# ESP_Robo_Board_2.net
KiCad netlist of a schematic drawn in EAGLE
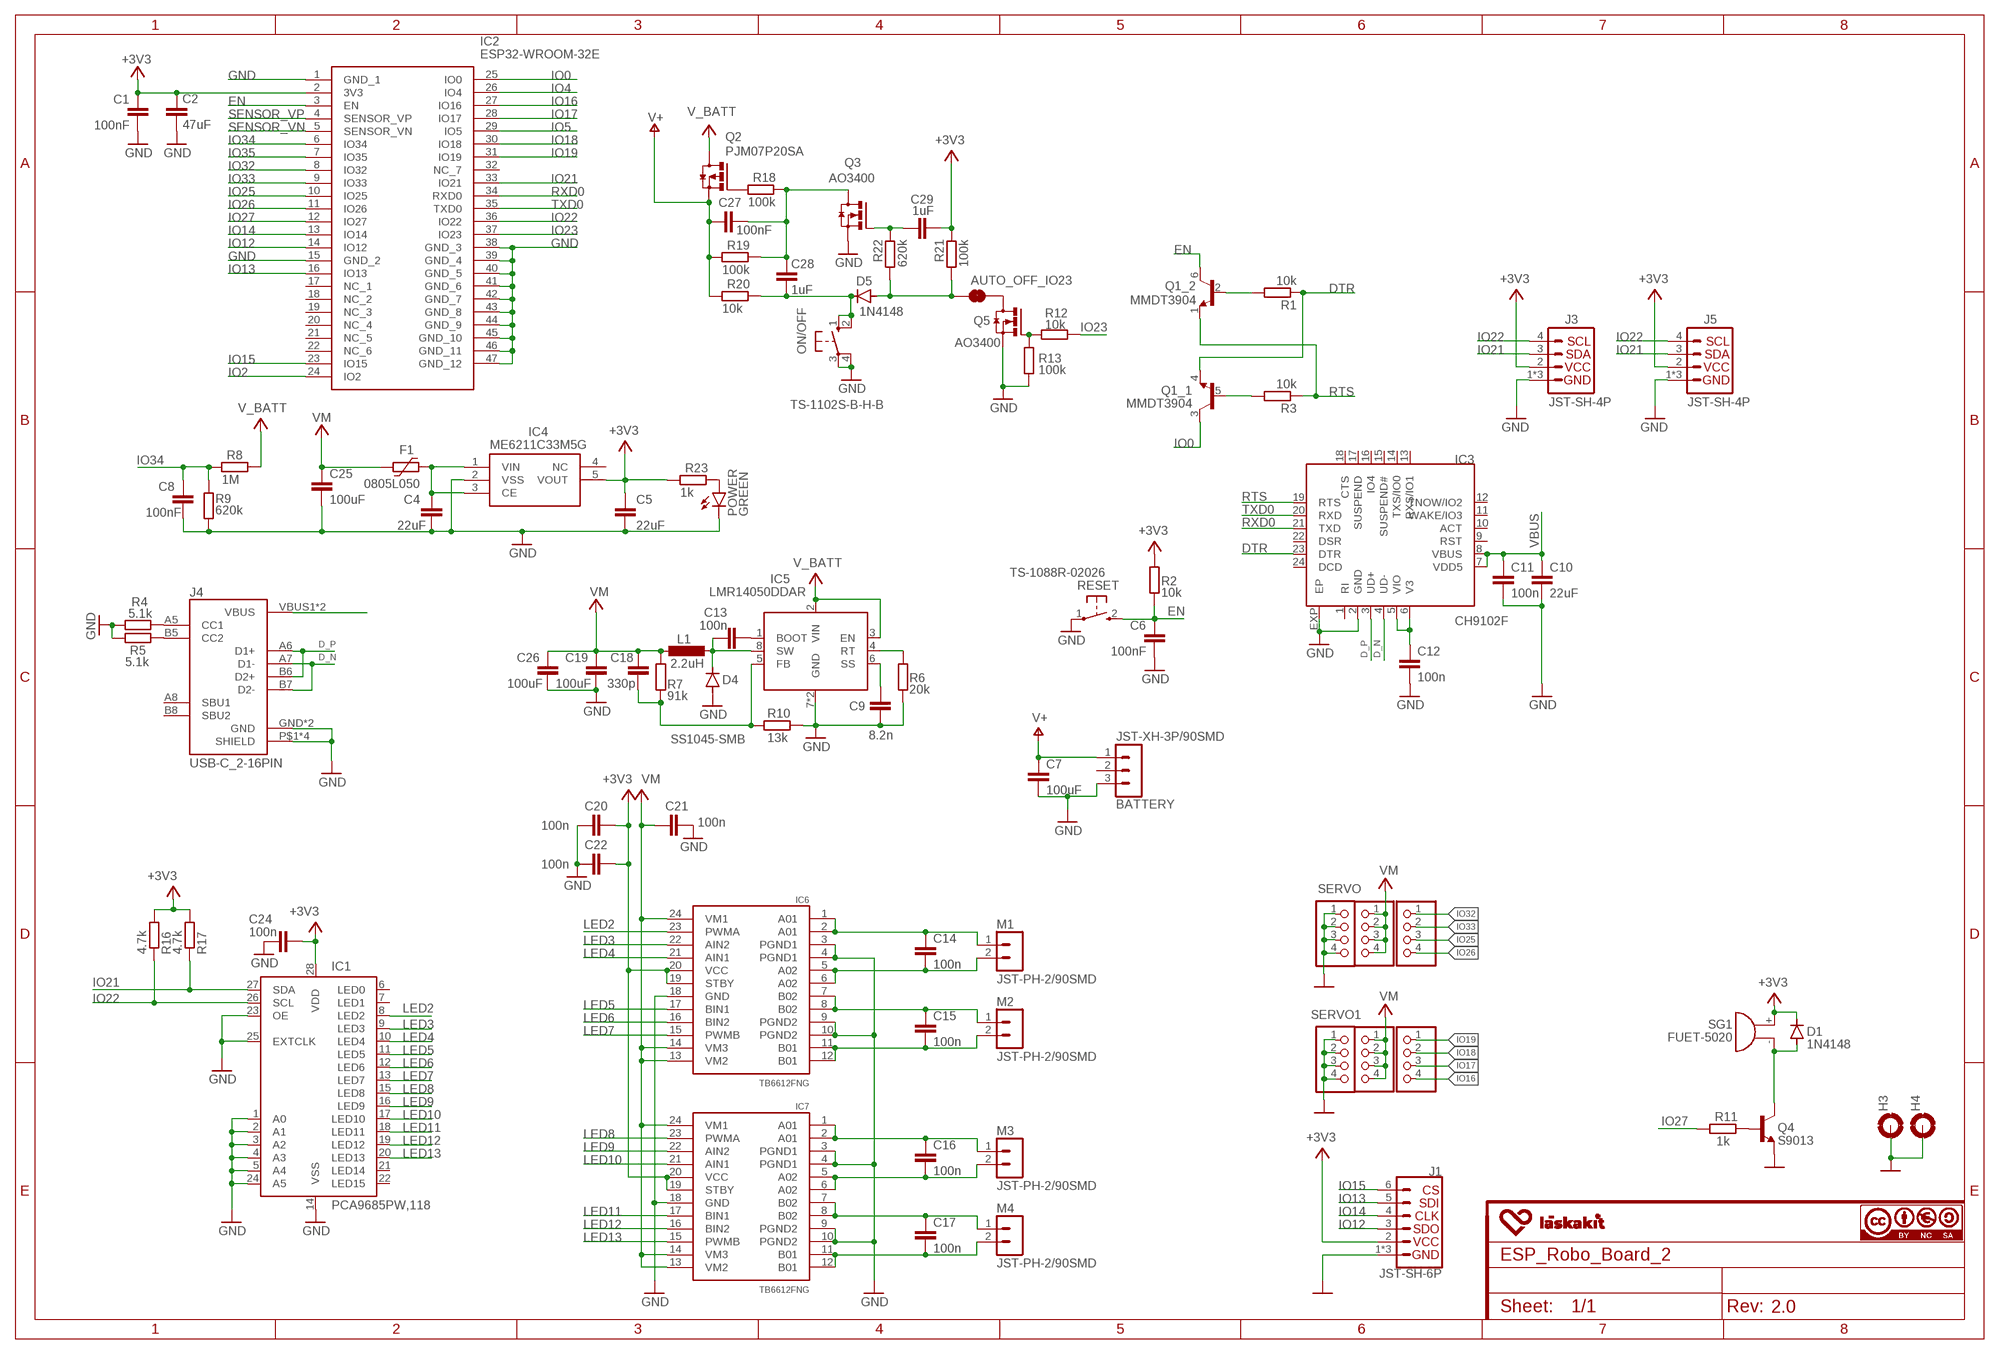
[diagram p0: schematic, sheet 1]

(export (version "E")
  (design (tool "Eeschema 10.0.6"))
  (components
    (comp (ref "1")
      (value "PINHD_1X4_RED")
      (footprint "eagle-import:1X04")
      (libsource (lib "eagle-import") (part "PINHD-1X4"))
    )
    (comp (ref "2")
      (value "PINHD_1X4_BLACK")
      (footprint "eagle-import:1X04")
      (libsource (lib "eagle-import") (part "PINHD-1X4"))
    )
    (comp (ref "5")
      (value "PINHD_1X4_RED")
      (footprint "eagle-import:1X04")
      (libsource (lib "eagle-import") (part "PINHD-1X4"))
    )
    (comp (ref "6")
      (value "PINHD_1X4_BLACK")
      (footprint "eagle-import:1X04")
      (libsource (lib "eagle-import") (part "PINHD-1X4"))
    )
    (comp (ref "AUTO_OFF_IO23")
      (value "nv")
      (footprint "eagle-import:SMT-JUMPER_2_NC_TRACE_SILK")
      (libsource (lib "eagle-import") (part "JUMPER-SMT_2_NC_TRACE_SILK"))
    )
    (comp (ref "BATTERY")
      (value "JST-XH-3P/90SMD")
      (footprint "eagle-import:S3B-XH-SM4")
      (libsource (lib "eagle-import") (part "JST-XH-3/90SMD"))
    )
    (comp (ref "C1")
      (value "100nF")
      (footprint "eagle-import:C0603")
      (libsource (lib "eagle-import") (part "C-EUC0603"))
    )
    (comp (ref "C2")
      (value "47uF")
      (footprint "eagle-import:C0805")
      (libsource (lib "eagle-import") (part "C-EUC0805"))
    )
    (comp (ref "C4")
      (value "22uF")
      (footprint "eagle-import:C0603")
      (libsource (lib "eagle-import") (part "C-EUC0603"))
    )
    (comp (ref "C5")
      (value "22uF")
      (footprint "eagle-import:C0603")
      (fields (field (name "LCSC_PART") "C19666"))
      (libsource (lib "eagle-import") (part "C-EUC0603"))
    )
    (comp (ref "C6")
      (value "100nF")
      (footprint "eagle-import:C0402")
      (libsource (lib "eagle-import") (part "CAPACITOR_0402"))
    )
    (comp (ref "C7")
      (value "100uF")
      (footprint "eagle-import:C1206")
      (libsource (lib "eagle-import") (part "C-EUC1206"))
    )
    (comp (ref "C8")
      (value "100nF")
      (footprint "eagle-import:C0402")
      (libsource (lib "eagle-import") (part "CAPACITOR_0402"))
    )
    (comp (ref "C9")
      (value "8.2n")
      (footprint "eagle-import:C0603")
      (libsource (lib "eagle-import") (part "C-EUC0603"))
    )
    (comp (ref "C10")
      (value "22uF")
      (footprint "eagle-import:C0603")
      (libsource (lib "eagle-import") (part "C-EUC0603"))
    )
    (comp (ref "C11")
      (value "100n")
      (footprint "eagle-import:C0402")
      (libsource (lib "eagle-import") (part "CAPACITOR_0402"))
    )
    (comp (ref "C12")
      (value "100n")
      (footprint "eagle-import:C0402")
      (libsource (lib "eagle-import") (part "CAPACITOR_0402"))
    )
    (comp (ref "C13")
      (value "100n")
      (footprint "eagle-import:C0603")
      (libsource (lib "eagle-import") (part "C-EUC0603"))
    )
    (comp (ref "C14")
      (value "100n")
      (footprint "eagle-import:C0603")
      (libsource (lib "eagle-import") (part "C-EUC0603"))
    )
    (comp (ref "C15")
      (value "100n")
      (footprint "eagle-import:C0603")
      (libsource (lib "eagle-import") (part "C-EUC0603"))
    )
    (comp (ref "C16")
      (value "100n")
      (footprint "eagle-import:C0603")
      (libsource (lib "eagle-import") (part "C-EUC0603"))
    )
    (comp (ref "C17")
      (value "100n")
      (footprint "eagle-import:C0603")
      (libsource (lib "eagle-import") (part "C-EUC0603"))
    )
    (comp (ref "C18")
      (value "330p")
      (footprint "eagle-import:C0402")
      (libsource (lib "eagle-import") (part "CAPACITOR_0402"))
    )
    (comp (ref "C19")
      (value "100uF")
      (footprint "eagle-import:C1206")
      (libsource (lib "eagle-import") (part "C-EUC1206"))
    )
    (comp (ref "C20")
      (value "100n")
      (footprint "eagle-import:C0603")
      (libsource (lib "eagle-import") (part "C-EUC0603"))
    )
    (comp (ref "C21")
      (value "100n")
      (footprint "eagle-import:C0603")
      (libsource (lib "eagle-import") (part "C-EUC0603"))
    )
    (comp (ref "C22")
      (value "100n")
      (footprint "eagle-import:C0603")
      (libsource (lib "eagle-import") (part "C-EUC0603"))
    )
    (comp (ref "C24")
      (value "100n")
      (footprint "eagle-import:C0603")
      (libsource (lib "eagle-import") (part "C-EUC0603"))
    )
    (comp (ref "C25")
      (value "100uF")
      (footprint "eagle-import:C1206")
      (libsource (lib "eagle-import") (part "C-EUC1206"))
    )
    (comp (ref "C26")
      (value "100uF")
      (footprint "eagle-import:C1206")
      (libsource (lib "eagle-import") (part "C-EUC1206"))
    )
    (comp (ref "C27")
      (value "100nF")
      (footprint "eagle-import:C0402")
      (libsource (lib "eagle-import") (part "CAPACITOR_0402"))
    )
    (comp (ref "C28")
      (value "1uF")
      (footprint "eagle-import:C0603")
      (libsource (lib "eagle-import") (part "C-EUC0603"))
    )
    (comp (ref "C29")
      (value "1uF")
      (footprint "eagle-import:C0603")
      (libsource (lib "eagle-import") (part "C-EUC0603"))
    )
    (comp (ref "D1")
      (value "1N4148")
      (footprint "eagle-import:SOD323-R")
      (fields (field (name "LCSC_PART") "C94001"))
      (libsource (lib "eagle-import") (part "DIODE-SOD323-R"))
    )
    (comp (ref "D4")
      (value "SS1045-SMB")
      (footprint "eagle-import:SMB")
      (fields (field (name "LCSC_PART") "C2903947"))
      (libsource (lib "eagle-import") (part "DIODE-SMB"))
    )
    (comp (ref "D5")
      (value "1N4148")
      (footprint "eagle-import:SOD323-R")
      (libsource (lib "eagle-import") (part "DIODE-SOD323-R"))
    )
    (comp (ref "F1")
      (value "0805L050")
      (footprint "eagle-import:0805L")
      (fields (field (name "MF") "Littelfuse") (field (name "LCSC_PART") "C66452"))
      (libsource (lib "eagle-import") (part "?0805L050"))
    )
    (comp (ref "H3")
      (value "MOUNT-PAD-ROUND2.5")
      (footprint "eagle-import:2,5-PAD")
      (libsource (lib "eagle-import") (part "MOUNT-PAD-ROUND2.5"))
    )
    (comp (ref "H4")
      (value "MOUNT-PAD-ROUND2.5")
      (footprint "eagle-import:2,5-PAD")
      (libsource (lib "eagle-import") (part "MOUNT-PAD-ROUND2.5"))
    )
    (comp (ref "IC1")
      (value "PCA9685PW,118")
      (footprint "eagle-import:TSSOP28")
      (fields (field (name "LCSC_PART") "C2678753"))
      (libsource (lib "eagle-import") (part "PCA9685PW,118"))
    )
    (comp (ref "IC2")
      (value "ESP32-WROOM-32E")
      (footprint "eagle-import:ESP32WROOM32E")
      (libsource (lib "eagle-import") (part "ESP32-WROOM-32E"))
    )
    (comp (ref "IC3")
      (value "CH9102F")
      (footprint "eagle-import:QFN24-4X4")
      (libsource (lib "eagle-import") (part "USB_UART_CONVERTOR_CH9102"))
    )
    (comp (ref "IC4")
      (value "ME6211C33M5G")
      (footprint "eagle-import:SOT23-5")
      (libsource (lib "eagle-import") (part "LDO_ME6211C33M5G"))
    )
    (comp (ref "IC5")
      (value "LMR14050DDAR")
      (footprint "eagle-import:SO08-EPAD")
      (fields (field (name "LCSC_PART") "C155484"))
      (libsource (lib "eagle-import") (part "LMR14050DDAR"))
    )
    (comp (ref "IC6")
      (value "TB6612FNG")
      (footprint "eagle-import:SSOP24")
      (libsource (lib "eagle-import") (part "MOTOR_DRIVER_TB6612FNG"))
    )
    (comp (ref "IC7")
      (value "TB6612FNG")
      (footprint "eagle-import:SSOP24")
      (libsource (lib "eagle-import") (part "MOTOR_DRIVER_TB6612FNG"))
    )
    (comp (ref "J1")
      (value "JST-SH-6P")
      (footprint "eagle-import:1X06_1MM_RA_VERT")
      (fields (field (name "LCSC_PART") "C145963"))
      (libsource (lib "eagle-import") (part "USUP_SPI_CONNECTOR_VERT"))
    )
    (comp (ref "J3")
      (value "JST-SH-4P")
      (footprint "eagle-import:1X04_1MM_RA_VERT")
      (fields (field (name "LCSC_PART") "C371588"))
      (libsource (lib "eagle-import") (part "USUP_I2C_CONNECTOR_VERT"))
    )
    (comp (ref "J4")
      (value "USB-C_2-16PIN")
      (footprint "eagle-import:USBC_USB-C-16P-5")
      (fields (field (name "LCSC_PART") "C2837092"))
      (libsource (lib "eagle-import") (part "USB-C_2-16PIN"))
    )
    (comp (ref "J5")
      (value "JST-SH-4P")
      (footprint "eagle-import:1X04_1MM_RA_VERT")
      (fields (field (name "LCSC_PART") "C371588"))
      (libsource (lib "eagle-import") (part "USUP_I2C_CONNECTOR_VERT"))
    )
    (comp (ref "L1")
      (value "2.2uH")
      (footprint "eagle-import:L5.4X5.2")
      (fields (field (name "LCSC_PART") "C351096"))
      (libsource (lib "eagle-import") (part "INDUCTOR_5.4X5.2"))
    )
    (comp (ref "M1")
      (value "JST-PH-2/90SMD")
      (footprint "eagle-import:S2B-PH-SM4")
      (fields (field (name "LCSC_PART") "C47647"))
      (libsource (lib "eagle-import") (part "JST-PH-2/90SMD"))
    )
    (comp (ref "M2")
      (value "JST-PH-2/90SMD")
      (footprint "eagle-import:S2B-PH-SM4")
      (fields (field (name "LCSC_PART") "C47647"))
      (libsource (lib "eagle-import") (part "JST-PH-2/90SMD"))
    )
    (comp (ref "M3")
      (value "JST-PH-2/90SMD")
      (footprint "eagle-import:S2B-PH-SM4")
      (fields (field (name "LCSC_PART") "C47647"))
      (libsource (lib "eagle-import") (part "JST-PH-2/90SMD"))
    )
    (comp (ref "M4")
      (value "JST-PH-2/90SMD")
      (footprint "eagle-import:S2B-PH-SM4")
      (fields (field (name "LCSC_PART") "C47647"))
      (libsource (lib "eagle-import") (part "JST-PH-2/90SMD"))
    )
    (comp (ref "ON/OFF")
      (value "TS-1102S-B-H-B")
      (footprint "eagle-import:B3F-SMD")
      (libsource (lib "eagle-import") (part "10-XX-SMD"))
    )
    (comp (ref "POWER")
      (value "GREEN")
      (footprint "eagle-import:CHIPLED_0402")
      (libsource (lib "eagle-import") (part "LEDCHIPLED_0402"))
    )
    (comp (ref "Q1")
      (value "MMDT3904")
      (footprint "eagle-import:SC70-6")
      (fields (field (name "LCSC_PART") "C268586"))
      (libsource (lib "eagle-import") (part "TRANS_NPN_DUAL-MBT3904DW1T1"))
    )
    (comp (ref "Q2")
      (value "PJM07P20SA")
      (footprint "eagle-import:SOT23")
      (fields (field (name "LCSC_PART") "C2856842"))
      (libsource (lib "eagle-import") (part "MOSFET_P-SOT-23"))
    )
    (comp (ref "Q3")
      (value "AO3400")
      (footprint "eagle-import:SOT23")
      (fields (field (name "LCSC_PART") "C693097"))
      (libsource (lib "eagle-import") (part "MOSFET_N-SOT-23"))
    )
    (comp (ref "Q4")
      (value "S9013")
      (footprint "eagle-import:SOT23-BEC")
      (fields (field (name "LCSC_PART") "C52801"))
      (libsource (lib "eagle-import") (part "-NPN-SOT23-BECBC817-16"))
    )
    (comp (ref "Q5")
      (value "AO3400")
      (footprint "eagle-import:SOT23")
      (fields (field (name "LCSC_PART") "C693097"))
      (libsource (lib "eagle-import") (part "MOSFET_N-SOT-23"))
    )
    (comp (ref "R1")
      (value "10k")
      (footprint "eagle-import:R0402")
      (libsource (lib "eagle-import") (part "R-EU_R0402"))
    )
    (comp (ref "R2")
      (value "10k")
      (footprint "eagle-import:R0402")
      (libsource (lib "eagle-import") (part "R-EU_R0402"))
    )
    (comp (ref "R3")
      (value "10k")
      (footprint "eagle-import:R0402")
      (libsource (lib "eagle-import") (part "R-EU_R0402"))
    )
    (comp (ref "R4")
      (value "5.1k")
      (footprint "eagle-import:R0402")
      (libsource (lib "eagle-import") (part "R-EU_R0402"))
    )
    (comp (ref "R5")
      (value "5.1k")
      (footprint "eagle-import:R0402")
      (libsource (lib "eagle-import") (part "R-EU_R0402"))
    )
    (comp (ref "R6")
      (value "20k")
      (footprint "eagle-import:R0402")
      (libsource (lib "eagle-import") (part "R-EU_R0402"))
    )
    (comp (ref "R7")
      (value "91k")
      (footprint "eagle-import:R0402")
      (libsource (lib "eagle-import") (part "R-EU_R0402"))
    )
    (comp (ref "R8")
      (value "1M")
      (footprint "eagle-import:R0402")
      (libsource (lib "eagle-import") (part "R-EU_R0402"))
    )
    (comp (ref "R9")
      (value "620k")
      (footprint "eagle-import:R0402")
      (libsource (lib "eagle-import") (part "R-EU_R0402"))
    )
    (comp (ref "R10")
      (value "13k")
      (footprint "eagle-import:R0402")
      (libsource (lib "eagle-import") (part "R-EU_R0402"))
    )
    (comp (ref "R11")
      (value "1k")
      (footprint "eagle-import:R0402")
      (fields (field (name "LCSC_PART") "C22548"))
      (libsource (lib "eagle-import") (part "R-EU_R0402"))
    )
    (comp (ref "R12")
      (value "10k")
      (footprint "eagle-import:R0402")
      (libsource (lib "eagle-import") (part "R-EU_R0402"))
    )
    (comp (ref "R13")
      (value "100k")
      (footprint "eagle-import:R0402")
      (libsource (lib "eagle-import") (part "R-EU_R0402"))
    )
    (comp (ref "R16")
      (value "4.7k")
      (footprint "eagle-import:R0402")
      (libsource (lib "eagle-import") (part "R-EU_R0402"))
    )
    (comp (ref "R17")
      (value "4.7k")
      (footprint "eagle-import:R0402")
      (libsource (lib "eagle-import") (part "R-EU_R0402"))
    )
    (comp (ref "R18")
      (value "100k")
      (footprint "eagle-import:R0402")
      (libsource (lib "eagle-import") (part "R-EU_R0402"))
    )
    (comp (ref "R19")
      (value "100k")
      (footprint "eagle-import:R0402")
      (libsource (lib "eagle-import") (part "R-EU_R0402"))
    )
    (comp (ref "R20")
      (value "10k")
      (footprint "eagle-import:R0402")
      (libsource (lib "eagle-import") (part "R-EU_R0402"))
    )
    (comp (ref "R21")
      (value "100k")
      (footprint "eagle-import:R0402")
      (libsource (lib "eagle-import") (part "R-EU_R0402"))
    )
    (comp (ref "R22")
      (value "620k")
      (footprint "eagle-import:R0402")
      (libsource (lib "eagle-import") (part "R-EU_R0402"))
    )
    (comp (ref "R23")
      (value "1k")
      (footprint "eagle-import:R0402")
      (libsource (lib "eagle-import") (part "R-EU_R0402"))
    )
    (comp (ref "RESET")
      (value "TS-1088R-02026")
      (footprint "eagle-import:TS1088R02026")
      (fields (field (name "LCSC_PART") "C455280"))
      (libsource (lib "eagle-import") (part "MOMENTARY_SWITCH_TS-1088R-02026"))
    )
    (comp (ref "SERVO")
      (value "PINHD_1X4_YELLOW")
      (footprint "eagle-import:1X04")
      (libsource (lib "eagle-import") (part "PINHD-1X4"))
    )
    (comp (ref "SERVO1")
      (value "PINHD_1X4_YELLOW")
      (footprint "eagle-import:1X04")
      (libsource (lib "eagle-import") (part "PINHD-1X4"))
    )
    (comp (ref "SG1")
      (value "FUET-5020")
      (footprint "eagle-import:FUET-5020")
      (fields (field (name "LCSC_PART") "C391029"))
      (libsource (lib "eagle-import") (part "PASSIVE_BUZZER_3V_FUET-5020"))
    )
  )
  (nets
    (net (code "1") (name "+3V3") (class "Default")
      (node (ref "C1") (pin "1") (pinfunction "1_1") (pintype "passive"))
      (node (ref "C2") (pin "1") (pinfunction "1_1") (pintype "passive"))
      (node (ref "C20") (pin "2") (pinfunction "2_2") (pintype "passive"))
      (node (ref "C22") (pin "2") (pinfunction "2_2") (pintype "passive"))
      (node (ref "C24") (pin "2") (pinfunction "2_2") (pintype "passive"))
      (node (ref "C29") (pin "1") (pinfunction "1_1") (pintype "passive"))
      (node (ref "C5") (pin "1") (pinfunction "1_1") (pintype "passive"))
      (node (ref "D1") (pin "C") (pinfunction "C_C") (pintype "passive"))
      (node (ref "IC1") (pin "28") (pinfunction "VDD_28") (pintype "bidirectional"))
      (node (ref "IC2") (pin "2") (pinfunction "3V3_2") (pintype "bidirectional"))
      (node (ref "IC4") (pin "5") (pinfunction "VOUT_5") (pintype "bidirectional"))
      (node (ref "IC6") (pin "19") (pinfunction "STBY_19") (pintype "bidirectional"))
      (node (ref "IC6") (pin "20") (pinfunction "VCC_20") (pintype "bidirectional"))
      (node (ref "IC7") (pin "19") (pinfunction "STBY_19") (pintype "bidirectional"))
      (node (ref "IC7") (pin "20") (pinfunction "VCC_20") (pintype "bidirectional"))
      (node (ref "J1") (pin "2") (pinfunction "VCC_2") (pintype "power_in"))
      (node (ref "J3") (pin "2") (pinfunction "VCC_2") (pintype "power_in"))
      (node (ref "J5") (pin "2") (pinfunction "VCC_2") (pintype "power_in"))
      (node (ref "R16") (pin "2") (pinfunction "2_2") (pintype "passive"))
      (node (ref "R17") (pin "2") (pinfunction "2_2") (pintype "passive"))
      (node (ref "R2") (pin "1") (pinfunction "1_1") (pintype "passive"))
      (node (ref "R21") (pin "2") (pinfunction "2_2") (pintype "passive"))
      (node (ref "R23") (pin "1") (pinfunction "1_1") (pintype "passive"))
      (node (ref "SG1") (pin "+") (pinfunction "+_+") (pintype "passive"))
    )
    (net (code "2") (name "/DTR") (class "Default")
      (node (ref "IC3") (pin "23") (pinfunction "DTR_23") (pintype "bidirectional"))
      (node (ref "Q1") (pin "4") (pinfunction "E_4") (pintype "passive"))
      (node (ref "R1") (pin "1") (pinfunction "1_1") (pintype "passive"))
    )
    (net (code "3") (name "/D_N") (class "Default")
      (node (ref "IC3") (pin "4") (pinfunction "UD-_4") (pintype "bidirectional"))
      (node (ref "J4") (pin "A7") (pinfunction "D1-_A7") (pintype "passive"))
      (node (ref "J4") (pin "B7") (pinfunction "D2-_B7") (pintype "passive"))
    )
    (net (code "4") (name "/D_P") (class "Default")
      (node (ref "IC3") (pin "3") (pinfunction "UD+_3") (pintype "bidirectional"))
      (node (ref "J4") (pin "A6") (pinfunction "D1+_A6") (pintype "passive"))
      (node (ref "J4") (pin "B6") (pinfunction "D2+_B6") (pintype "passive"))
    )
    (net (code "5") (name "/EN") (class "Default")
      (node (ref "C6") (pin "1") (pinfunction "1_1") (pintype "passive"))
      (node (ref "IC2") (pin "3") (pinfunction "EN_3") (pintype "bidirectional"))
      (node (ref "Q1") (pin "6") (pinfunction "C_6") (pintype "passive"))
      (node (ref "R2") (pin "2") (pinfunction "2_2") (pintype "passive"))
      (node (ref "RESET") (pin "2") (pinfunction "3_2") (pintype "passive"))
    )
    (net (code "6") (name "/IO0") (class "Default")
      (node (ref "IC2") (pin "25") (pinfunction "IO0_25") (pintype "bidirectional"))
      (node (ref "Q1") (pin "3") (pinfunction "C_3") (pintype "passive"))
    )
    (net (code "7") (name "/IO2") (class "Default")
      (node (ref "IC2") (pin "24") (pinfunction "IO2_24") (pintype "bidirectional"))
    )
    (net (code "8") (name "/IO4") (class "Default")
      (node (ref "IC2") (pin "26") (pinfunction "IO4_26") (pintype "bidirectional"))
    )
    (net (code "9") (name "/IO5") (class "Default")
      (node (ref "IC2") (pin "29") (pinfunction "IO5_29") (pintype "bidirectional"))
    )
    (net (code "10") (name "/IO12") (class "Default")
      (node (ref "IC2") (pin "14") (pinfunction "IO12_14") (pintype "bidirectional"))
      (node (ref "J1") (pin "3") (pinfunction "SDO_3") (pintype "passive"))
    )
    (net (code "11") (name "/IO13") (class "Default")
      (node (ref "IC2") (pin "16") (pinfunction "IO13_16") (pintype "bidirectional"))
      (node (ref "J1") (pin "5") (pinfunction "SDI_5") (pintype "passive"))
    )
    (net (code "12") (name "/IO14") (class "Default")
      (node (ref "IC2") (pin "13") (pinfunction "IO14_13") (pintype "bidirectional"))
      (node (ref "J1") (pin "4") (pinfunction "CLK_4") (pintype "passive"))
    )
    (net (code "13") (name "/IO15") (class "Default")
      (node (ref "IC2") (pin "23") (pinfunction "IO15_23") (pintype "bidirectional"))
      (node (ref "J1") (pin "6") (pinfunction "CS_6") (pintype "passive"))
    )
    (net (code "14") (name "/IO21") (class "Default")
      (node (ref "IC1") (pin "27") (pinfunction "SDA_27") (pintype "bidirectional"))
      (node (ref "IC2") (pin "33") (pinfunction "IO21_33") (pintype "bidirectional"))
      (node (ref "J3") (pin "3") (pinfunction "SDA_3") (pintype "passive"))
      (node (ref "J5") (pin "3") (pinfunction "SDA_3") (pintype "passive"))
      (node (ref "R17") (pin "1") (pinfunction "1_1") (pintype "passive"))
    )
    (net (code "15") (name "/IO22") (class "Default")
      (node (ref "IC1") (pin "26") (pinfunction "SCL_26") (pintype "bidirectional"))
      (node (ref "IC2") (pin "36") (pinfunction "IO22_36") (pintype "bidirectional"))
      (node (ref "J3") (pin "4") (pinfunction "SCL_4") (pintype "passive"))
      (node (ref "J5") (pin "4") (pinfunction "SCL_4") (pintype "passive"))
      (node (ref "R16") (pin "1") (pinfunction "1_1") (pintype "passive"))
    )
    (net (code "16") (name "/IO23") (class "Default")
      (node (ref "IC2") (pin "37") (pinfunction "IO23_37") (pintype "bidirectional"))
      (node (ref "R12") (pin "2") (pinfunction "2_2") (pintype "passive"))
    )
    (net (code "17") (name "/IO27") (class "Default")
      (node (ref "IC2") (pin "12") (pinfunction "IO27_12") (pintype "bidirectional"))
      (node (ref "R11") (pin "1") (pinfunction "1_1") (pintype "passive"))
    )
    (net (code "18") (name "/IO34") (class "Default")
      (node (ref "C8") (pin "1") (pinfunction "1_1") (pintype "passive"))
      (node (ref "IC2") (pin "6") (pinfunction "IO34_6") (pintype "bidirectional"))
      (node (ref "R8") (pin "1") (pinfunction "1_1") (pintype "passive"))
      (node (ref "R9") (pin "2") (pinfunction "2_2") (pintype "passive"))
    )
    (net (code "19") (name "/IO35") (class "Default")
      (node (ref "IC2") (pin "7") (pinfunction "IO35_7") (pintype "bidirectional"))
    )
    (net (code "20") (name "/LED2") (class "Default")
      (node (ref "IC1") (pin "8") (pinfunction "LED2_8") (pintype "bidirectional"))
      (node (ref "IC6") (pin "23") (pinfunction "PWMA_23") (pintype "bidirectional"))
    )
    (net (code "21") (name "/LED3") (class "Default")
      (node (ref "IC1") (pin "9") (pinfunction "LED3_9") (pintype "bidirectional"))
      (node (ref "IC6") (pin "22") (pinfunction "AIN2_22") (pintype "bidirectional"))
    )
    (net (code "22") (name "/LED4") (class "Default")
      (node (ref "IC1") (pin "10") (pinfunction "LED4_10") (pintype "bidirectional"))
      (node (ref "IC6") (pin "21") (pinfunction "AIN1_21") (pintype "bidirectional"))
    )
    (net (code "23") (name "/LED5") (class "Default")
      (node (ref "IC1") (pin "11") (pinfunction "LED5_11") (pintype "bidirectional"))
      (node (ref "IC6") (pin "17") (pinfunction "BIN1_17") (pintype "bidirectional"))
    )
    (net (code "24") (name "/LED6") (class "Default")
      (node (ref "IC1") (pin "12") (pinfunction "LED6_12") (pintype "bidirectional"))
      (node (ref "IC6") (pin "16") (pinfunction "BIN2_16") (pintype "bidirectional"))
    )
    (net (code "25") (name "/LED7") (class "Default")
      (node (ref "IC1") (pin "13") (pinfunction "LED7_13") (pintype "bidirectional"))
      (node (ref "IC6") (pin "15") (pinfunction "PWMB_15") (pintype "bidirectional"))
    )
    (net (code "26") (name "/LED8") (class "Default")
      (node (ref "IC1") (pin "15") (pinfunction "LED8_15") (pintype "bidirectional"))
      (node (ref "IC7") (pin "23") (pinfunction "PWMA_23") (pintype "bidirectional"))
    )
    (net (code "27") (name "/LED9") (class "Default")
      (node (ref "IC1") (pin "16") (pinfunction "LED9_16") (pintype "bidirectional"))
      (node (ref "IC7") (pin "22") (pinfunction "AIN2_22") (pintype "bidirectional"))
    )
    (net (code "28") (name "/LED10") (class "Default")
      (node (ref "IC1") (pin "17") (pinfunction "LED10_17") (pintype "bidirectional"))
      (node (ref "IC7") (pin "21") (pinfunction "AIN1_21") (pintype "bidirectional"))
    )
    (net (code "29") (name "/LED11") (class "Default")
      (node (ref "IC1") (pin "18") (pinfunction "LED11_18") (pintype "bidirectional"))
      (node (ref "IC7") (pin "17") (pinfunction "BIN1_17") (pintype "bidirectional"))
    )
    (net (code "30") (name "/LED12") (class "Default")
      (node (ref "IC1") (pin "19") (pinfunction "LED12_19") (pintype "bidirectional"))
      (node (ref "IC7") (pin "16") (pinfunction "BIN2_16") (pintype "bidirectional"))
    )
    (net (code "31") (name "/LED13") (class "Default")
      (node (ref "IC1") (pin "20") (pinfunction "LED13_20") (pintype "bidirectional"))
      (node (ref "IC7") (pin "15") (pinfunction "PWMB_15") (pintype "bidirectional"))
    )
    (net (code "32") (name "/RTS") (class "Default")
      (node (ref "IC3") (pin "19") (pinfunction "RTS_19") (pintype "bidirectional"))
      (node (ref "Q1") (pin "1") (pinfunction "E_1") (pintype "passive"))
      (node (ref "R3") (pin "1") (pinfunction "1_1") (pintype "passive"))
    )
    (net (code "33") (name "/RXD0") (class "Default")
      (node (ref "IC2") (pin "34") (pinfunction "RXD0_34") (pintype "bidirectional"))
      (node (ref "IC3") (pin "21") (pinfunction "TXD_21") (pintype "bidirectional"))
    )
    (net (code "34") (name "/SENSOR_VN") (class "Default")
      (node (ref "IC2") (pin "5") (pinfunction "SENSOR_VN_5") (pintype "bidirectional"))
    )
    (net (code "35") (name "/SENSOR_VP") (class "Default")
      (node (ref "IC2") (pin "4") (pinfunction "SENSOR_VP_4") (pintype "bidirectional"))
    )
    (net (code "36") (name "/TXD0") (class "Default")
      (node (ref "IC2") (pin "35") (pinfunction "TXD0_35") (pintype "bidirectional"))
      (node (ref "IC3") (pin "20") (pinfunction "RXD_20") (pintype "bidirectional"))
    )
    (net (code "37") (name "/VBUS") (class "Default")
      (node (ref "C10") (pin "1") (pinfunction "1_1") (pintype "passive"))
      (node (ref "C11") (pin "1") (pinfunction "1_1") (pintype "passive"))
      (node (ref "IC3") (pin "7") (pinfunction "VDD5_7") (pintype "bidirectional"))
      (node (ref "IC3") (pin "8") (pinfunction "VBUS_8") (pintype "bidirectional"))
      (node (ref "J4") (pin "VBUS1") (pinfunction "VBUS_VBUS1") (pintype "passive"))
      (node (ref "J4") (pin "VBUS2") (pinfunction "VBUS_VBUS2") (pintype "passive"))
    )
    (net (code "38") (name "GND") (class "Default")
      (node (ref "2") (pin "1") (pinfunction "1_1") (pintype "passive"))
      (node (ref "2") (pin "2") (pinfunction "2_2") (pintype "passive"))
      (node (ref "2") (pin "3") (pinfunction "3_3") (pintype "passive"))
      (node (ref "2") (pin "4") (pinfunction "4_4") (pintype "passive"))
      (node (ref "6") (pin "1") (pinfunction "1_1") (pintype "passive"))
      (node (ref "6") (pin "2") (pinfunction "2_2") (pintype "passive"))
      (node (ref "6") (pin "3") (pinfunction "3_3") (pintype "passive"))
      (node (ref "6") (pin "4") (pinfunction "4_4") (pintype "passive"))
      (node (ref "BATTERY") (pin "3") (pinfunction "1_3") (pintype "passive"))
      (node (ref "C1") (pin "2") (pinfunction "2_2") (pintype "passive"))
      (node (ref "C10") (pin "2") (pinfunction "2_2") (pintype "passive"))
      (node (ref "C11") (pin "2") (pinfunction "2_2") (pintype "passive"))
      (node (ref "C12") (pin "2") (pinfunction "2_2") (pintype "passive"))
      (node (ref "C19") (pin "2") (pinfunction "2_2") (pintype "passive"))
      (node (ref "C2") (pin "2") (pinfunction "2_2") (pintype "passive"))
      (node (ref "C20") (pin "1") (pinfunction "1_1") (pintype "passive"))
      (node (ref "C21") (pin "2") (pinfunction "2_2") (pintype "passive"))
      (node (ref "C22") (pin "1") (pinfunction "1_1") (pintype "passive"))
      (node (ref "C24") (pin "1") (pinfunction "1_1") (pintype "passive"))
      (node (ref "C25") (pin "2") (pinfunction "2_2") (pintype "passive"))
      (node (ref "C26") (pin "2") (pinfunction "2_2") (pintype "passive"))
      (node (ref "C4") (pin "2") (pinfunction "2_2") (pintype "passive"))
      (node (ref "C5") (pin "2") (pinfunction "2_2") (pintype "passive"))
      (node (ref "C6") (pin "2") (pinfunction "2_2") (pintype "passive"))
      (node (ref "C7") (pin "2") (pinfunction "2_2") (pintype "passive"))
      (node (ref "C8") (pin "2") (pinfunction "2_2") (pintype "passive"))
      (node (ref "C9") (pin "2") (pinfunction "2_2") (pintype "passive"))
      (node (ref "D4") (pin "A") (pinfunction "A_A") (pintype "passive"))
      (node (ref "H3") (pin "1") (pinfunction "MOUNT_1") (pintype "passive"))
      (node (ref "H4") (pin "1") (pinfunction "MOUNT_1") (pintype "passive"))
      (node (ref "IC1") (pin "1") (pinfunction "A0_1") (pintype "bidirectional"))
      (node (ref "IC1") (pin "14") (pinfunction "VSS_14") (pintype "bidirectional"))
      (node (ref "IC1") (pin "2") (pinfunction "A1_2") (pintype "bidirectional"))
      (node (ref "IC1") (pin "23") (pinfunction "OE_23") (pintype "bidirectional"))
      (node (ref "IC1") (pin "24") (pinfunction "A5_24") (pintype "bidirectional"))
      (node (ref "IC1") (pin "25") (pinfunction "EXTCLK_25") (pintype "bidirectional"))
      (node (ref "IC1") (pin "3") (pinfunction "A2_3") (pintype "bidirectional"))
      (node (ref "IC1") (pin "4") (pinfunction "A3_4") (pintype "bidirectional"))
      (node (ref "IC1") (pin "5") (pinfunction "A4_5") (pintype "bidirectional"))
      (node (ref "IC2") (pin "1") (pinfunction "GND_1_1") (pintype "bidirectional"))
      (node (ref "IC2") (pin "15") (pinfunction "GND_2_15") (pintype "bidirectional"))
      (node (ref "IC2") (pin "38") (pinfunction "GND_3_38") (pintype "bidirectional"))
      (node (ref "IC2") (pin "39") (pinfunction "GND_4_39") (pintype "bidirectional"))
      (node (ref "IC2") (pin "40") (pinfunction "GND_5_40") (pintype "bidirectional"))
      (node (ref "IC2") (pin "41") (pinfunction "GND_6_41") (pintype "bidirectional"))
      (node (ref "IC2") (pin "42") (pinfunction "GND_7_42") (pintype "bidirectional"))
      (node (ref "IC2") (pin "43") (pinfunction "GND_8_43") (pintype "bidirectional"))
      (node (ref "IC2") (pin "44") (pinfunction "GND_9_44") (pintype "bidirectional"))
      (node (ref "IC2") (pin "45") (pinfunction "GND_10_45") (pintype "bidirectional"))
      (node (ref "IC2") (pin "46") (pinfunction "GND_11_46") (pintype "bidirectional"))
      (node (ref "IC2") (pin "47") (pinfunction "GND_12_47") (pintype "bidirectional"))
      (node (ref "IC3") (pin "2") (pinfunction "GND_2") (pintype "bidirectional"))
      (node (ref "IC3") (pin "EXP") (pinfunction "EP_EXP") (pintype "bidirectional"))
      (node (ref "IC4") (pin "2") (pinfunction "VSS_2") (pintype "bidirectional"))
      (node (ref "IC5") (pin "7") (pinfunction "GND_7") (pintype "bidirectional"))
      (node (ref "IC5") (pin "EPAD") (pinfunction "GND_EPAD") (pintype "bidirectional"))
      (node (ref "IC6") (pin "10") (pinfunction "PGND2_10") (pintype "bidirectional"))
      (node (ref "IC6") (pin "18") (pinfunction "GND_18") (pintype "bidirectional"))
      (node (ref "IC6") (pin "3") (pinfunction "PGND1_3") (pintype "bidirectional"))
      (node (ref "IC6") (pin "4") (pinfunction "PGND1_4") (pintype "bidirectional"))
      (node (ref "IC6") (pin "9") (pinfunction "PGND2_9") (pintype "bidirectional"))
      (node (ref "IC7") (pin "10") (pinfunction "PGND2_10") (pintype "bidirectional"))
      (node (ref "IC7") (pin "18") (pinfunction "GND_18") (pintype "bidirectional"))
      (node (ref "IC7") (pin "3") (pinfunction "PGND1_3") (pintype "bidirectional"))
      (node (ref "IC7") (pin "4") (pinfunction "PGND1_4") (pintype "bidirectional"))
      (node (ref "IC7") (pin "9") (pinfunction "PGND2_9") (pintype "bidirectional"))
      (node (ref "J1") (pin "1") (pinfunction "GND_1") (pintype "power_in"))
      (node (ref "J1") (pin "NC1") (pinfunction "GND_NC1") (pintype "power_in"))
      (node (ref "J1") (pin "NC2") (pinfunction "GND_NC2") (pintype "power_in"))
      (node (ref "J3") (pin "1") (pinfunction "GND_1") (pintype "power_in"))
      (node (ref "J3") (pin "NC1") (pinfunction "GND_NC1") (pintype "power_in"))
      (node (ref "J3") (pin "NC2") (pinfunction "GND_NC2") (pintype "power_in"))
      (node (ref "J4") (pin "GND") (pinfunction "GND_GND") (pintype "passive"))
      (node (ref "J4") (pin "GND2") (pinfunction "GND_GND2") (pintype "passive"))
      (node (ref "J4") (pin "P$1") (pinfunction "SHIELD_P$1") (pintype "passive"))
      (node (ref "J4") (pin "P$2") (pinfunction "SHIELD_P$2") (pintype "passive"))
      (node (ref "J4") (pin "P$3") (pinfunction "SHIELD_P$3") (pintype "passive"))
      (node (ref "J4") (pin "P$4") (pinfunction "SHIELD_P$4") (pintype "passive"))
      (node (ref "J5") (pin "1") (pinfunction "GND_1") (pintype "power_in"))
      (node (ref "J5") (pin "NC1") (pinfunction "GND_NC1") (pintype "power_in"))
      (node (ref "J5") (pin "NC2") (pinfunction "GND_NC2") (pintype "power_in"))
      (node (ref "ON/OFF") (pin "3") (pinfunction "P_3") (pintype "passive"))
      (node (ref "ON/OFF") (pin "4") (pinfunction "P1_4") (pintype "passive"))
      (node (ref "POWER") (pin "C") (pinfunction "C_C") (pintype "passive"))
      (node (ref "Q3") (pin "2") (pinfunction "S_2") (pintype "passive"))
      (node (ref "Q4") (pin "E") (pinfunction "E_E") (pintype "passive"))
      (node (ref "Q5") (pin "2") (pinfunction "S_2") (pintype "passive"))
      (node (ref "R10") (pin "2") (pinfunction "2_2") (pintype "passive"))
      (node (ref "R13") (pin "1") (pinfunction "1_1") (pintype "passive"))
      (node (ref "R4") (pin "1") (pinfunction "1_1") (pintype "passive"))
      (node (ref "R5") (pin "1") (pinfunction "1_1") (pintype "passive"))
      (node (ref "R6") (pin "2") (pinfunction "2_2") (pintype "passive"))
      (node (ref "R9") (pin "1") (pinfunction "1_1") (pintype "passive"))
      (node (ref "RESET") (pin "1") (pinfunction "1_1") (pintype "passive"))
    )
    (net (code "39") (name "IO16") (class "Default")
      (node (ref "IC2") (pin "27") (pinfunction "IO16_27") (pintype "bidirectional"))
      (node (ref "SERVO1") (pin "4") (pinfunction "4_4") (pintype "passive"))
    )
    (net (code "40") (name "IO17") (class "Default")
      (node (ref "IC2") (pin "28") (pinfunction "IO17_28") (pintype "bidirectional"))
      (node (ref "SERVO1") (pin "3") (pinfunction "3_3") (pintype "passive"))
    )
    (net (code "41") (name "IO18") (class "Default")
      (node (ref "IC2") (pin "30") (pinfunction "IO18_30") (pintype "bidirectional"))
      (node (ref "SERVO1") (pin "2") (pinfunction "2_2") (pintype "passive"))
    )
    (net (code "42") (name "IO19") (class "Default")
      (node (ref "IC2") (pin "31") (pinfunction "IO19_31") (pintype "bidirectional"))
      (node (ref "SERVO1") (pin "1") (pinfunction "1_1") (pintype "passive"))
    )
    (net (code "43") (name "IO25") (class "Default")
      (node (ref "IC2") (pin "10") (pinfunction "IO25_10") (pintype "bidirectional"))
      (node (ref "SERVO") (pin "3") (pinfunction "3_3") (pintype "passive"))
    )
    (net (code "44") (name "IO26") (class "Default")
      (node (ref "IC2") (pin "11") (pinfunction "IO26_11") (pintype "bidirectional"))
      (node (ref "SERVO") (pin "4") (pinfunction "4_4") (pintype "passive"))
    )
    (net (code "45") (name "IO32") (class "Default")
      (node (ref "IC2") (pin "8") (pinfunction "IO32_8") (pintype "bidirectional"))
      (node (ref "SERVO") (pin "1") (pinfunction "1_1") (pintype "passive"))
    )
    (net (code "46") (name "IO33") (class "Default")
      (node (ref "IC2") (pin "9") (pinfunction "IO33_9") (pintype "bidirectional"))
      (node (ref "SERVO") (pin "2") (pinfunction "2_2") (pintype "passive"))
    )
    (net (code "47") (name "Net-(AUTO_OFF_IO23-Pad1)") (class "Default")
      (node (ref "AUTO_OFF_IO23") (pin "1") (pinfunction "1_1") (pintype "passive"))
      (node (ref "D5") (pin "A") (pinfunction "A_A") (pintype "passive"))
      (node (ref "R21") (pin "1") (pinfunction "1_1") (pintype "passive"))
      (node (ref "R22") (pin "1") (pinfunction "1_1") (pintype "passive"))
    )
    (net (code "48") (name "Net-(C14-Pad1)") (class "Default")
      (node (ref "C14") (pin "1") (pinfunction "1_1") (pintype "passive"))
      (node (ref "IC6") (pin "1") (pinfunction "A01_1") (pintype "bidirectional"))
      (node (ref "IC6") (pin "2") (pinfunction "A01_2") (pintype "bidirectional"))
      (node (ref "M1") (pin "1") (pinfunction "1_1") (pintype "passive"))
    )
    (net (code "49") (name "Net-(C14-Pad2)") (class "Default")
      (node (ref "C14") (pin "2") (pinfunction "2_2") (pintype "passive"))
      (node (ref "IC6") (pin "5") (pinfunction "A02_5") (pintype "bidirectional"))
      (node (ref "IC6") (pin "6") (pinfunction "A02_6") (pintype "bidirectional"))
      (node (ref "M1") (pin "2") (pinfunction "2_2") (pintype "passive"))
    )
    (net (code "50") (name "Net-(C15-Pad1)") (class "Default")
      (node (ref "C15") (pin "1") (pinfunction "1_1") (pintype "passive"))
      (node (ref "IC6") (pin "7") (pinfunction "B02_7") (pintype "bidirectional"))
      (node (ref "IC6") (pin "8") (pinfunction "B02_8") (pintype "bidirectional"))
      (node (ref "M2") (pin "1") (pinfunction "1_1") (pintype "passive"))
    )
    (net (code "51") (name "Net-(C15-Pad2)") (class "Default")
      (node (ref "C15") (pin "2") (pinfunction "2_2") (pintype "passive"))
      (node (ref "IC6") (pin "11") (pinfunction "B01_11") (pintype "bidirectional"))
      (node (ref "IC6") (pin "12") (pinfunction "B01_12") (pintype "bidirectional"))
      (node (ref "M2") (pin "2") (pinfunction "2_2") (pintype "passive"))
    )
    (net (code "52") (name "Net-(C16-Pad1)") (class "Default")
      (node (ref "C16") (pin "1") (pinfunction "1_1") (pintype "passive"))
      (node (ref "IC7") (pin "1") (pinfunction "A01_1") (pintype "bidirectional"))
      (node (ref "IC7") (pin "2") (pinfunction "A01_2") (pintype "bidirectional"))
      (node (ref "M3") (pin "1") (pinfunction "1_1") (pintype "passive"))
    )
    (net (code "53") (name "Net-(C16-Pad2)") (class "Default")
      (node (ref "C16") (pin "2") (pinfunction "2_2") (pintype "passive"))
      (node (ref "IC7") (pin "5") (pinfunction "A02_5") (pintype "bidirectional"))
      (node (ref "IC7") (pin "6") (pinfunction "A02_6") (pintype "bidirectional"))
      (node (ref "M3") (pin "2") (pinfunction "2_2") (pintype "passive"))
    )
    (net (code "54") (name "Net-(C17-Pad1)") (class "Default")
      (node (ref "C17") (pin "1") (pinfunction "1_1") (pintype "passive"))
      (node (ref "IC7") (pin "7") (pinfunction "B02_7") (pintype "bidirectional"))
      (node (ref "IC7") (pin "8") (pinfunction "B02_8") (pintype "bidirectional"))
      (node (ref "M4") (pin "1") (pinfunction "1_1") (pintype "passive"))
    )
    (net (code "55") (name "Net-(C17-Pad2)") (class "Default")
      (node (ref "C17") (pin "2") (pinfunction "2_2") (pintype "passive"))
      (node (ref "IC7") (pin "11") (pinfunction "B01_11") (pintype "bidirectional"))
      (node (ref "IC7") (pin "12") (pinfunction "B01_12") (pintype "bidirectional"))
      (node (ref "M4") (pin "2") (pinfunction "2_2") (pintype "passive"))
    )
    (net (code "56") (name "Net-(D1-PadA)") (class "Default")
      (node (ref "D1") (pin "A") (pinfunction "A_A") (pintype "passive"))
      (node (ref "Q4") (pin "C") (pinfunction "C_C") (pintype "passive"))
      (node (ref "SG1") (pin "-") (pinfunction "-_-") (pintype "passive"))
    )
    (net (code "57") (name "Net-(IC3-V3)") (class "Default")
      (node (ref "C12") (pin "1") (pinfunction "1_1") (pintype "passive"))
      (node (ref "IC3") (pin "5") (pinfunction "VIO_5") (pintype "bidirectional"))
      (node (ref "IC3") (pin "6") (pinfunction "V3_6") (pintype "bidirectional"))
    )
    (net (code "58") (name "Net-(IC4-CE)") (class "Default")
      (node (ref "C4") (pin "1") (pinfunction "1_1") (pintype "passive"))
      (node (ref "F1") (pin "1") (pinfunction "1_1") (pintype "passive"))
      (node (ref "IC4") (pin "1") (pinfunction "VIN_1") (pintype "bidirectional"))
      (node (ref "IC4") (pin "3") (pinfunction "CE_3") (pintype "bidirectional"))
    )
    (net (code "59") (name "Net-(IC5-BOOT)") (class "Default")
      (node (ref "C13") (pin "2") (pinfunction "2_2") (pintype "passive"))
      (node (ref "IC5") (pin "1") (pinfunction "BOOT_1") (pintype "bidirectional"))
    )
    (net (code "60") (name "Net-(IC5-FB)") (class "Default")
      (node (ref "C18") (pin "2") (pinfunction "2_2") (pintype "passive"))
      (node (ref "IC5") (pin "5") (pinfunction "FB_5") (pintype "bidirectional"))
      (node (ref "R10") (pin "1") (pinfunction "1_1") (pintype "passive"))
      (node (ref "R7") (pin "2") (pinfunction "2_2") (pintype "passive"))
    )
    (net (code "61") (name "Net-(IC5-RT)") (class "Default")
      (node (ref "IC5") (pin "4") (pinfunction "RT_4") (pintype "bidirectional"))
      (node (ref "R6") (pin "1") (pinfunction "1_1") (pintype "passive"))
    )
    (net (code "62") (name "Net-(IC5-SS)") (class "Default")
      (node (ref "C9") (pin "1") (pinfunction "1_1") (pintype "passive"))
      (node (ref "IC5") (pin "6") (pinfunction "SS_6") (pintype "bidirectional"))
    )
    (net (code "63") (name "Net-(IC5-SW)") (class "Default")
      (node (ref "C13") (pin "1") (pinfunction "1_1") (pintype "passive"))
      (node (ref "D4") (pin "C") (pinfunction "C_C") (pintype "passive"))
      (node (ref "IC5") (pin "8") (pinfunction "SW_8") (pintype "bidirectional"))
      (node (ref "L1") (pin "1") (pinfunction "1_1") (pintype "passive"))
    )
    (net (code "64") (name "Net-(J4-CC1)") (class "Default")
      (node (ref "J4") (pin "A5") (pinfunction "CC1_A5") (pintype "passive"))
      (node (ref "R4") (pin "2") (pinfunction "2_2") (pintype "passive"))
    )
    (net (code "65") (name "Net-(J4-CC2)") (class "Default")
      (node (ref "J4") (pin "B5") (pinfunction "CC2_B5") (pintype "passive"))
      (node (ref "R5") (pin "2") (pinfunction "2_2") (pintype "passive"))
    )
    (net (code "66") (name "Net-(ON/OFF-S)") (class "Default")
      (node (ref "C28") (pin "2") (pinfunction "2_2") (pintype "passive"))
      (node (ref "D5") (pin "C") (pinfunction "C_C") (pintype "passive"))
      (node (ref "ON/OFF") (pin "1") (pinfunction "S_1") (pintype "passive"))
      (node (ref "ON/OFF") (pin "2") (pinfunction "S1_2") (pintype "passive"))
      (node (ref "R20") (pin "2") (pinfunction "2_2") (pintype "passive"))
    )
    (net (code "67") (name "Net-(POWER-PadA)") (class "Default")
      (node (ref "POWER") (pin "A") (pinfunction "A_A") (pintype "passive"))
      (node (ref "R23") (pin "2") (pinfunction "2_2") (pintype "passive"))
    )
    (net (code "68") (name "Net-(Q1A-B)") (class "Default")
      (node (ref "Q1") (pin "5") (pinfunction "B_5") (pintype "passive"))
      (node (ref "R3") (pin "2") (pinfunction "2_2") (pintype "passive"))
    )
    (net (code "69") (name "Net-(Q1B-B)") (class "Default")
      (node (ref "Q1") (pin "2") (pinfunction "B_2") (pintype "passive"))
      (node (ref "R1") (pin "2") (pinfunction "2_2") (pintype "passive"))
    )
    (net (code "70") (name "Net-(Q2-G)") (class "Default")
      (node (ref "Q2") (pin "1") (pinfunction "G_1") (pintype "passive"))
      (node (ref "R18") (pin "1") (pinfunction "1_1") (pintype "passive"))
    )
    (net (code "71") (name "Net-(Q3-D)") (class "Default")
      (node (ref "C27") (pin "2") (pinfunction "2_2") (pintype "passive"))
      (node (ref "C28") (pin "1") (pinfunction "1_1") (pintype "passive"))
      (node (ref "Q3") (pin "3") (pinfunction "D_3") (pintype "passive"))
      (node (ref "R18") (pin "2") (pinfunction "2_2") (pintype "passive"))
      (node (ref "R19") (pin "2") (pinfunction "2_2") (pintype "passive"))
    )
    (net (code "72") (name "Net-(Q3-G)") (class "Default")
      (node (ref "C29") (pin "2") (pinfunction "2_2") (pintype "passive"))
      (node (ref "Q3") (pin "1") (pinfunction "G_1") (pintype "passive"))
      (node (ref "R22") (pin "2") (pinfunction "2_2") (pintype "passive"))
    )
    (net (code "73") (name "Net-(Q4-PadB)") (class "Default")
      (node (ref "Q4") (pin "B") (pinfunction "B_B") (pintype "passive"))
      (node (ref "R11") (pin "2") (pinfunction "2_2") (pintype "passive"))
    )
    (net (code "74") (name "Net-(Q5-D)") (class "Default")
      (node (ref "AUTO_OFF_IO23") (pin "2") (pinfunction "2_2") (pintype "passive"))
      (node (ref "Q5") (pin "3") (pinfunction "D_3") (pintype "passive"))
    )
    (net (code "75") (name "Net-(Q5-G)") (class "Default")
      (node (ref "Q5") (pin "1") (pinfunction "G_1") (pintype "passive"))
      (node (ref "R12") (pin "1") (pinfunction "1_1") (pintype "passive"))
      (node (ref "R13") (pin "2") (pinfunction "2_2") (pintype "passive"))
    )
    (net (code "76") (name "V+") (class "Default")
      (node (ref "BATTERY") (pin "1") (pinfunction "3_1") (pintype "passive"))
      (node (ref "C27") (pin "1") (pinfunction "1_1") (pintype "passive"))
      (node (ref "C7") (pin "1") (pinfunction "1_1") (pintype "passive"))
      (node (ref "Q2") (pin "2") (pinfunction "S_2") (pintype "passive"))
      (node (ref "R19") (pin "1") (pinfunction "1_1") (pintype "passive"))
      (node (ref "R20") (pin "1") (pinfunction "1_1") (pintype "passive"))
    )
    (net (code "77") (name "VM") (class "Default")
      (node (ref "1") (pin "1") (pinfunction "1_1") (pintype "passive"))
      (node (ref "1") (pin "2") (pinfunction "2_2") (pintype "passive"))
      (node (ref "1") (pin "3") (pinfunction "3_3") (pintype "passive"))
      (node (ref "1") (pin "4") (pinfunction "4_4") (pintype "passive"))
      (node (ref "5") (pin "1") (pinfunction "1_1") (pintype "passive"))
      (node (ref "5") (pin "2") (pinfunction "2_2") (pintype "passive"))
      (node (ref "5") (pin "3") (pinfunction "3_3") (pintype "passive"))
      (node (ref "5") (pin "4") (pinfunction "4_4") (pintype "passive"))
      (node (ref "C18") (pin "1") (pinfunction "1_1") (pintype "passive"))
      (node (ref "C19") (pin "1") (pinfunction "1_1") (pintype "passive"))
      (node (ref "C21") (pin "1") (pinfunction "1_1") (pintype "passive"))
      (node (ref "C25") (pin "1") (pinfunction "1_1") (pintype "passive"))
      (node (ref "C26") (pin "1") (pinfunction "1_1") (pintype "passive"))
      (node (ref "F1") (pin "2") (pinfunction "2_2") (pintype "passive"))
      (node (ref "IC6") (pin "13") (pinfunction "VM2_13") (pintype "bidirectional"))
      (node (ref "IC6") (pin "14") (pinfunction "VM3_14") (pintype "bidirectional"))
      (node (ref "IC6") (pin "24") (pinfunction "VM1_24") (pintype "bidirectional"))
      (node (ref "IC7") (pin "13") (pinfunction "VM2_13") (pintype "bidirectional"))
      (node (ref "IC7") (pin "14") (pinfunction "VM3_14") (pintype "bidirectional"))
      (node (ref "IC7") (pin "24") (pinfunction "VM1_24") (pintype "bidirectional"))
      (node (ref "L1") (pin "2") (pinfunction "2_2") (pintype "passive"))
      (node (ref "R7") (pin "1") (pinfunction "1_1") (pintype "passive"))
    )
    (net (code "78") (name "V_BATT") (class "Default")
      (node (ref "IC5") (pin "2") (pinfunction "VIN_2") (pintype "bidirectional"))
      (node (ref "IC5") (pin "3") (pinfunction "EN_3") (pintype "bidirectional"))
      (node (ref "Q2") (pin "3") (pinfunction "D_3") (pintype "passive"))
      (node (ref "R8") (pin "2") (pinfunction "2_2") (pintype "passive"))
    )
    (net (code "79") (name "unconnected-(BATTERY-Pad2)") (class "Default")
      (node (ref "BATTERY") (pin "2") (pinfunction "2_2") (pintype "passive"))
    )
    (net (code "80") (name "unconnected-(IC1-LED0-Pad6)") (class "Default")
      (node (ref "IC1") (pin "6") (pinfunction "LED0_6") (pintype "bidirectional"))
    )
    (net (code "81") (name "unconnected-(IC1-LED1-Pad7)") (class "Default")
      (node (ref "IC1") (pin "7") (pinfunction "LED1_7") (pintype "bidirectional"))
    )
    (net (code "82") (name "unconnected-(IC1-LED14-Pad21)") (class "Default")
      (node (ref "IC1") (pin "21") (pinfunction "LED14_21") (pintype "bidirectional"))
    )
    (net (code "83") (name "unconnected-(IC1-LED15-Pad22)") (class "Default")
      (node (ref "IC1") (pin "22") (pinfunction "LED15_22") (pintype "bidirectional"))
    )
    (net (code "84") (name "unconnected-(IC2-NC_1-Pad17)") (class "Default")
      (node (ref "IC2") (pin "17") (pinfunction "NC_1_17") (pintype "bidirectional"))
    )
    (net (code "85") (name "unconnected-(IC2-NC_2-Pad18)") (class "Default")
      (node (ref "IC2") (pin "18") (pinfunction "NC_2_18") (pintype "bidirectional"))
    )
    (net (code "86") (name "unconnected-(IC2-NC_3-Pad19)") (class "Default")
      (node (ref "IC2") (pin "19") (pinfunction "NC_3_19") (pintype "bidirectional"))
    )
    (net (code "87") (name "unconnected-(IC2-NC_4-Pad20)") (class "Default")
      (node (ref "IC2") (pin "20") (pinfunction "NC_4_20") (pintype "bidirectional"))
    )
    (net (code "88") (name "unconnected-(IC2-NC_5-Pad21)") (class "Default")
      (node (ref "IC2") (pin "21") (pinfunction "NC_5_21") (pintype "bidirectional"))
    )
    (net (code "89") (name "unconnected-(IC2-NC_6-Pad22)") (class "Default")
      (node (ref "IC2") (pin "22") (pinfunction "NC_6_22") (pintype "bidirectional"))
    )
    (net (code "90") (name "unconnected-(IC2-NC_7-Pad32)") (class "Default")
      (node (ref "IC2") (pin "32") (pinfunction "NC_7_32") (pintype "no_connect"))
    )
    (net (code "91") (name "unconnected-(IC3-ACT-Pad10)") (class "Default")
      (node (ref "IC3") (pin "10") (pinfunction "ACT_10") (pintype "bidirectional"))
    )
    (net (code "92") (name "unconnected-(IC3-CTS-Pad18)") (class "Default")
      (node (ref "IC3") (pin "18") (pinfunction "CTS_18") (pintype "bidirectional"))
    )
    (net (code "93") (name "unconnected-(IC3-DCD-Pad24)") (class "Default")
      (node (ref "IC3") (pin "24") (pinfunction "DCD_24") (pintype "bidirectional"))
    )
    (net (code "94") (name "unconnected-(IC3-DSR-Pad22)") (class "Default")
      (node (ref "IC3") (pin "22") (pinfunction "DSR_22") (pintype "bidirectional"))
    )
    (net (code "95") (name "unconnected-(IC3-IO4-Pad16)") (class "Default")
      (node (ref "IC3") (pin "16") (pinfunction "IO4_16") (pintype "bidirectional"))
    )
    (net (code "96") (name "unconnected-(IC3-RI-Pad1)") (class "Default")
      (node (ref "IC3") (pin "1") (pinfunction "RI_1") (pintype "bidirectional"))
    )
    (net (code "97") (name "unconnected-(IC3-RST-Pad9)") (class "Default")
      (node (ref "IC3") (pin "9") (pinfunction "RST_9") (pintype "bidirectional"))
    )
    (net (code "98") (name "unconnected-(IC3-RXS{slash}IO1-Pad13)") (class "Default")
      (node (ref "IC3") (pin "13") (pinfunction "RXS/IO1_13") (pintype "bidirectional"))
    )
    (net (code "99") (name "unconnected-(IC3-SUSPEND#-Pad15)") (class "Default")
      (node (ref "IC3") (pin "15") (pinfunction "SUSPEND#_15") (pintype "bidirectional"))
    )
    (net (code "100") (name "unconnected-(IC3-SUSPEND-Pad17)") (class "Default")
      (node (ref "IC3") (pin "17") (pinfunction "SUSPEND_17") (pintype "bidirectional"))
    )
    (net (code "101") (name "unconnected-(IC3-TNOW{slash}IO2-Pad12)") (class "Default")
      (node (ref "IC3") (pin "12") (pinfunction "TNOW/IO2_12") (pintype "bidirectional"))
    )
    (net (code "102") (name "unconnected-(IC3-TXS{slash}IO0-Pad14)") (class "Default")
      (node (ref "IC3") (pin "14") (pinfunction "TXS/IO0_14") (pintype "bidirectional"))
    )
    (net (code "103") (name "unconnected-(IC3-WAKE{slash}IO3-Pad11)") (class "Default")
      (node (ref "IC3") (pin "11") (pinfunction "WAKE/IO3_11") (pintype "bidirectional"))
    )
    (net (code "104") (name "unconnected-(IC4-NC-Pad4)") (class "Default")
      (node (ref "IC4") (pin "4") (pinfunction "NC_4") (pintype "no_connect"))
    )
    (net (code "105") (name "unconnected-(J4-SBU1-PadA8)") (class "Default")
      (node (ref "J4") (pin "A8") (pinfunction "SBU1_A8") (pintype "passive"))
    )
    (net (code "106") (name "unconnected-(J4-SBU2-PadB8)") (class "Default")
      (node (ref "J4") (pin "B8") (pinfunction "SBU2_B8") (pintype "passive"))
    )
  )
)
